# small_esc.net
KiCad netlist of a schematic drawn in EAGLE
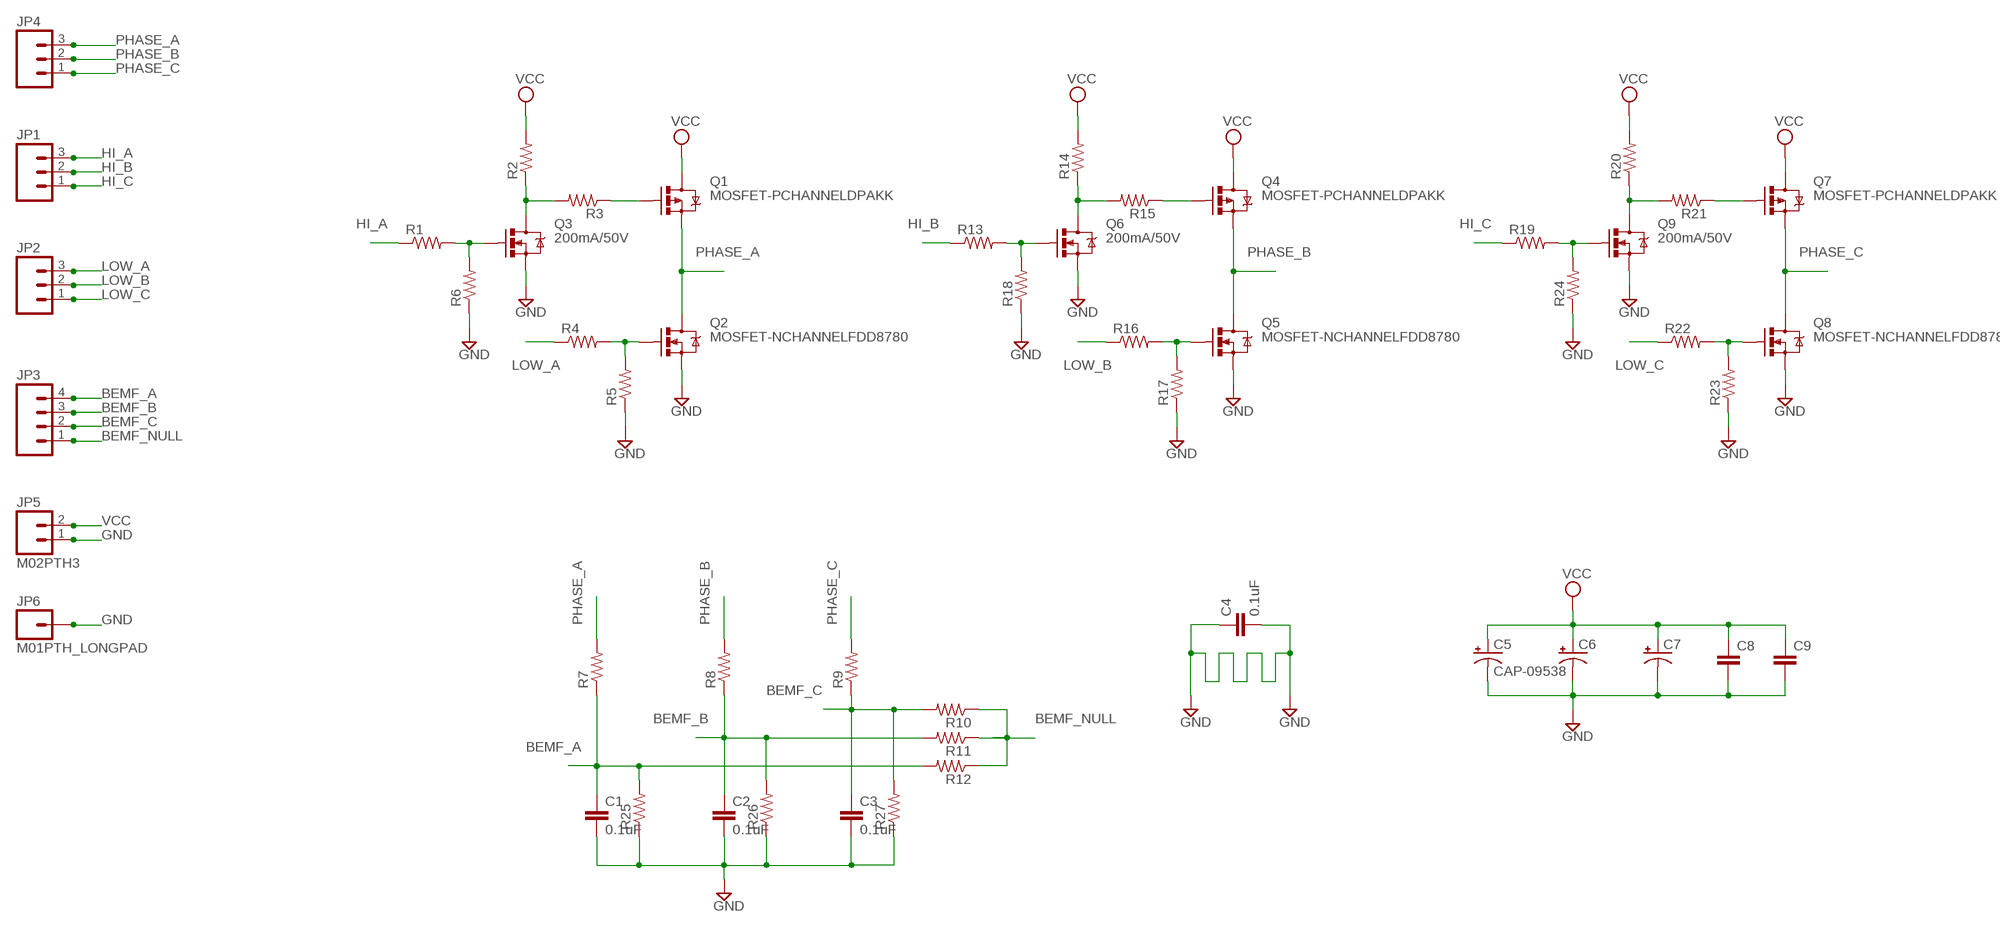
[diagram p0: schematic, sheet 1]

(export (version "E")
  (design (tool "Eeschema 10.0.6"))
  (components
    (comp (ref "C1")
      (value "0.1uF")
      (footprint "eagle-import:0603-CAP")
      (libsource (lib "eagle-import") (part "0.1UF-25V(+80/-20%)(0603)"))
    )
    (comp (ref "C2")
      (value "0.1uF")
      (footprint "eagle-import:0603-CAP")
      (libsource (lib "eagle-import") (part "0.1UF-25V(+80/-20%)(0603)"))
    )
    (comp (ref "C3")
      (value "0.1uF")
      (footprint "eagle-import:0603-CAP")
      (libsource (lib "eagle-import") (part "0.1UF-25V(+80/-20%)(0603)"))
    )
    (comp (ref "C4")
      (value "0.1uF")
      (footprint "eagle-import:0603-CAP")
      (libsource (lib "eagle-import") (part "0.1UF-25V(+80/-20%)(0603)"))
    )
    (comp (ref "C5")
      (value "CAP-09538")
      (footprint "eagle-import:CPOL-RADIAL-1000UF-25V")
      (libsource (lib "eagle-import") (part "1000UF-25V(PTH)"))
    )
    (comp (ref "C6")
      (value "CAP_POLPTH2")
      (footprint "eagle-import:CPOL-RADIAL-10UF-25V")
      (libsource (lib "eagle-import") (part "CAP_POLPTH2"))
    )
    (comp (ref "C7")
      (value "CAP_POLPTH2")
      (footprint "eagle-import:CPOL-RADIAL-10UF-25V")
      (libsource (lib "eagle-import") (part "CAP_POLPTH2"))
    )
    (comp (ref "C8")
      (value "0.1UF-50V-20%(PTH)KIT-EZ")
      (footprint "eagle-import:CAP-PTH-SMALL-KIT")
      (libsource (lib "eagle-import") (part "0.1UF-50V-20%(PTH)KIT-EZ"))
    )
    (comp (ref "C9")
      (value "0.1UF-50V-20%(PTH)KIT-EZ")
      (footprint "eagle-import:CAP-PTH-SMALL-KIT")
      (libsource (lib "eagle-import") (part "0.1UF-50V-20%(PTH)KIT-EZ"))
    )
    (comp (ref "JP1")
      (value "M03LONGPADS")
      (footprint "eagle-import:1X03_LONGPADS")
      (libsource (lib "eagle-import") (part "M03LONGPADS"))
    )
    (comp (ref "JP2")
      (value "M03LONGPADS")
      (footprint "eagle-import:1X03_LONGPADS")
      (libsource (lib "eagle-import") (part "M03LONGPADS"))
    )
    (comp (ref "JP3")
      (value "M04LONGPADS")
      (footprint "eagle-import:1X04_LONGPADS")
      (libsource (lib "eagle-import") (part "M04LONGPADS"))
    )
    (comp (ref "JP4")
      (value "M03LONGPADS")
      (footprint "eagle-import:1X03_LONGPADS")
      (libsource (lib "eagle-import") (part "M03LONGPADS"))
    )
    (comp (ref "JP5")
      (value "M02PTH3")
      (footprint "eagle-import:1X02_LONGPADS")
      (libsource (lib "eagle-import") (part "M02PTH3"))
    )
    (comp (ref "JP6")
      (value "M01PTH_LONGPAD")
      (footprint "eagle-import:1X01_LONGPAD")
      (libsource (lib "eagle-import") (part "M01PTH_LONGPAD"))
    )
    (comp (ref "Q1")
      (value "MOSFET-PCHANNELDPAKK")
      (footprint "eagle-import:DPAK")
      (libsource (lib "eagle-import") (part "MOSFET-PCHANNELDPAKK"))
    )
    (comp (ref "Q2")
      (value "MOSFET-NCHANNELFDD8780")
      (footprint "eagle-import:DPAK")
      (libsource (lib "eagle-import") (part "MOSFET-NCHANNELFDD8780"))
    )
    (comp (ref "Q3")
      (value "200mA/50V")
      (footprint "eagle-import:SOT23-3")
      (libsource (lib "eagle-import") (part "MOSFET-NCHANNELBSS138"))
    )
    (comp (ref "Q4")
      (value "MOSFET-PCHANNELDPAKK")
      (footprint "eagle-import:DPAK")
      (libsource (lib "eagle-import") (part "MOSFET-PCHANNELDPAKK"))
    )
    (comp (ref "Q5")
      (value "MOSFET-NCHANNELFDD8780")
      (footprint "eagle-import:DPAK")
      (libsource (lib "eagle-import") (part "MOSFET-NCHANNELFDD8780"))
    )
    (comp (ref "Q6")
      (value "200mA/50V")
      (footprint "eagle-import:SOT23-3")
      (libsource (lib "eagle-import") (part "MOSFET-NCHANNELBSS138"))
    )
    (comp (ref "Q7")
      (value "MOSFET-PCHANNELDPAKK")
      (footprint "eagle-import:DPAK")
      (libsource (lib "eagle-import") (part "MOSFET-PCHANNELDPAKK"))
    )
    (comp (ref "Q8")
      (value "MOSFET-NCHANNELFDD8780")
      (footprint "eagle-import:DPAK")
      (libsource (lib "eagle-import") (part "MOSFET-NCHANNELFDD8780"))
    )
    (comp (ref "Q9")
      (value "200mA/50V")
      (footprint "eagle-import:SOT23-3")
      (libsource (lib "eagle-import") (part "MOSFET-NCHANNELBSS138"))
    )
    (comp (ref "R1")
      (value "RESISTOR0603")
      (footprint "eagle-import:0603-RES")
      (libsource (lib "eagle-import") (part "RESISTOR0603"))
    )
    (comp (ref "R2")
      (value "RESISTOR0603")
      (footprint "eagle-import:0603-RES")
      (libsource (lib "eagle-import") (part "RESISTOR0603"))
    )
    (comp (ref "R3")
      (value "RESISTOR0603")
      (footprint "eagle-import:0603-RES")
      (libsource (lib "eagle-import") (part "RESISTOR0603"))
    )
    (comp (ref "R4")
      (value "RESISTOR0603")
      (footprint "eagle-import:0603-RES")
      (libsource (lib "eagle-import") (part "RESISTOR0603"))
    )
    (comp (ref "R5")
      (value "RESISTOR0603")
      (footprint "eagle-import:0603-RES")
      (libsource (lib "eagle-import") (part "RESISTOR0603"))
    )
    (comp (ref "R6")
      (value "RESISTOR0603")
      (footprint "eagle-import:0603-RES")
      (libsource (lib "eagle-import") (part "RESISTOR0603"))
    )
    (comp (ref "R7")
      (value "RESISTOR0603")
      (footprint "eagle-import:0603-RES")
      (libsource (lib "eagle-import") (part "RESISTOR0603"))
    )
    (comp (ref "R8")
      (value "RESISTOR0603")
      (footprint "eagle-import:0603-RES")
      (libsource (lib "eagle-import") (part "RESISTOR0603"))
    )
    (comp (ref "R9")
      (value "RESISTOR0603")
      (footprint "eagle-import:0603-RES")
      (libsource (lib "eagle-import") (part "RESISTOR0603"))
    )
    (comp (ref "R10")
      (value "RESISTOR0603")
      (footprint "eagle-import:0603-RES")
      (libsource (lib "eagle-import") (part "RESISTOR0603"))
    )
    (comp (ref "R11")
      (value "RESISTOR0603")
      (footprint "eagle-import:0603-RES")
      (libsource (lib "eagle-import") (part "RESISTOR0603"))
    )
    (comp (ref "R12")
      (value "RESISTOR0603")
      (footprint "eagle-import:0603-RES")
      (libsource (lib "eagle-import") (part "RESISTOR0603"))
    )
    (comp (ref "R13")
      (value "RESISTOR0603")
      (footprint "eagle-import:0603-RES")
      (libsource (lib "eagle-import") (part "RESISTOR0603"))
    )
    (comp (ref "R14")
      (value "RESISTOR0603")
      (footprint "eagle-import:0603-RES")
      (libsource (lib "eagle-import") (part "RESISTOR0603"))
    )
    (comp (ref "R15")
      (value "RESISTOR0603")
      (footprint "eagle-import:0603-RES")
      (libsource (lib "eagle-import") (part "RESISTOR0603"))
    )
    (comp (ref "R16")
      (value "RESISTOR0603")
      (footprint "eagle-import:0603-RES")
      (libsource (lib "eagle-import") (part "RESISTOR0603"))
    )
    (comp (ref "R17")
      (value "RESISTOR0603")
      (footprint "eagle-import:0603-RES")
      (libsource (lib "eagle-import") (part "RESISTOR0603"))
    )
    (comp (ref "R18")
      (value "RESISTOR0603")
      (footprint "eagle-import:0603-RES")
      (libsource (lib "eagle-import") (part "RESISTOR0603"))
    )
    (comp (ref "R19")
      (value "RESISTOR0603")
      (footprint "eagle-import:0603-RES")
      (libsource (lib "eagle-import") (part "RESISTOR0603"))
    )
    (comp (ref "R20")
      (value "RESISTOR0603")
      (footprint "eagle-import:0603-RES")
      (libsource (lib "eagle-import") (part "RESISTOR0603"))
    )
    (comp (ref "R21")
      (value "RESISTOR0603")
      (footprint "eagle-import:0603-RES")
      (libsource (lib "eagle-import") (part "RESISTOR0603"))
    )
    (comp (ref "R22")
      (value "RESISTOR0603")
      (footprint "eagle-import:0603-RES")
      (libsource (lib "eagle-import") (part "RESISTOR0603"))
    )
    (comp (ref "R23")
      (value "RESISTOR0603")
      (footprint "eagle-import:0603-RES")
      (libsource (lib "eagle-import") (part "RESISTOR0603"))
    )
    (comp (ref "R24")
      (value "RESISTOR0603")
      (footprint "eagle-import:0603-RES")
      (libsource (lib "eagle-import") (part "RESISTOR0603"))
    )
    (comp (ref "R25")
      (value "RESISTOR0603")
      (footprint "eagle-import:0603-RES")
      (libsource (lib "eagle-import") (part "RESISTOR0603"))
    )
    (comp (ref "R26")
      (value "RESISTOR0603")
      (footprint "eagle-import:0603-RES")
      (libsource (lib "eagle-import") (part "RESISTOR0603"))
    )
    (comp (ref "R27")
      (value "RESISTOR0603")
      (footprint "eagle-import:0603-RES")
      (libsource (lib "eagle-import") (part "RESISTOR0603"))
    )
  )
  (nets
    (net (code "1") (name "/BEMF_A") (class "Default")
      (node (ref "C1") (pin "1") (pinfunction "1_1") (pintype "passive"))
      (node (ref "JP3") (pin "4") (pinfunction "4_4") (pintype "passive"))
      (node (ref "R12") (pin "2") (pinfunction "2_2") (pintype "passive"))
      (node (ref "R25") (pin "2") (pinfunction "2_2") (pintype "passive"))
      (node (ref "R7") (pin "1") (pinfunction "1_1") (pintype "passive"))
    )
    (net (code "2") (name "/BEMF_B") (class "Default")
      (node (ref "C2") (pin "1") (pinfunction "1_1") (pintype "passive"))
      (node (ref "JP3") (pin "3") (pinfunction "3_3") (pintype "passive"))
      (node (ref "R11") (pin "2") (pinfunction "2_2") (pintype "passive"))
      (node (ref "R26") (pin "2") (pinfunction "2_2") (pintype "passive"))
      (node (ref "R8") (pin "1") (pinfunction "1_1") (pintype "passive"))
    )
    (net (code "3") (name "/BEMF_C") (class "Default")
      (node (ref "C3") (pin "1") (pinfunction "1_1") (pintype "passive"))
      (node (ref "JP3") (pin "2") (pinfunction "2_2") (pintype "passive"))
      (node (ref "R10") (pin "2") (pinfunction "2_2") (pintype "passive"))
      (node (ref "R27") (pin "2") (pinfunction "2_2") (pintype "passive"))
      (node (ref "R9") (pin "1") (pinfunction "1_1") (pintype "passive"))
    )
    (net (code "4") (name "/BEMF_NULL") (class "Default")
      (node (ref "JP3") (pin "1") (pinfunction "1_1") (pintype "passive"))
      (node (ref "R10") (pin "1") (pinfunction "1_1") (pintype "passive"))
      (node (ref "R11") (pin "1") (pinfunction "1_1") (pintype "passive"))
      (node (ref "R12") (pin "1") (pinfunction "1_1") (pintype "passive"))
    )
    (net (code "5") (name "/HI_A") (class "Default")
      (node (ref "JP1") (pin "3") (pinfunction "3_3") (pintype "passive"))
      (node (ref "R1") (pin "1") (pinfunction "1_1") (pintype "passive"))
    )
    (net (code "6") (name "/HI_B") (class "Default")
      (node (ref "JP1") (pin "2") (pinfunction "2_2") (pintype "passive"))
      (node (ref "R13") (pin "1") (pinfunction "1_1") (pintype "passive"))
    )
    (net (code "7") (name "/HI_C") (class "Default")
      (node (ref "JP1") (pin "1") (pinfunction "1_1") (pintype "passive"))
      (node (ref "R19") (pin "1") (pinfunction "1_1") (pintype "passive"))
    )
    (net (code "8") (name "/LOW_A") (class "Default")
      (node (ref "JP2") (pin "3") (pinfunction "3_3") (pintype "passive"))
      (node (ref "R4") (pin "1") (pinfunction "1_1") (pintype "passive"))
    )
    (net (code "9") (name "/LOW_B") (class "Default")
      (node (ref "JP2") (pin "2") (pinfunction "2_2") (pintype "passive"))
      (node (ref "R16") (pin "1") (pinfunction "1_1") (pintype "passive"))
    )
    (net (code "10") (name "/LOW_C") (class "Default")
      (node (ref "JP2") (pin "1") (pinfunction "1_1") (pintype "passive"))
      (node (ref "R22") (pin "1") (pinfunction "1_1") (pintype "passive"))
    )
    (net (code "11") (name "/PHASE_A") (class "Default")
      (node (ref "JP4") (pin "3") (pinfunction "3_3") (pintype "passive"))
      (node (ref "Q1") (pin "4") (pinfunction "S_4") (pintype "passive"))
      (node (ref "Q2") (pin "4") (pinfunction "D_4") (pintype "passive"))
      (node (ref "R7") (pin "2") (pinfunction "2_2") (pintype "passive"))
    )
    (net (code "12") (name "/PHASE_B") (class "Default")
      (node (ref "JP4") (pin "2") (pinfunction "2_2") (pintype "passive"))
      (node (ref "Q4") (pin "4") (pinfunction "S_4") (pintype "passive"))
      (node (ref "Q5") (pin "4") (pinfunction "D_4") (pintype "passive"))
      (node (ref "R8") (pin "2") (pinfunction "2_2") (pintype "passive"))
    )
    (net (code "13") (name "/PHASE_C") (class "Default")
      (node (ref "JP4") (pin "1") (pinfunction "1_1") (pintype "passive"))
      (node (ref "Q7") (pin "4") (pinfunction "S_4") (pintype "passive"))
      (node (ref "Q8") (pin "4") (pinfunction "D_4") (pintype "passive"))
      (node (ref "R9") (pin "2") (pinfunction "2_2") (pintype "passive"))
    )
    (net (code "14") (name "GND") (class "Default")
      (node (ref "C1") (pin "2") (pinfunction "2_2") (pintype "passive"))
      (node (ref "C2") (pin "2") (pinfunction "2_2") (pintype "passive"))
      (node (ref "C3") (pin "2") (pinfunction "2_2") (pintype "passive"))
      (node (ref "C4") (pin "1") (pinfunction "1_1") (pintype "passive"))
      (node (ref "C4") (pin "2") (pinfunction "2_2") (pintype "passive"))
      (node (ref "C5") (pin "-") (pinfunction "-_-") (pintype "passive"))
      (node (ref "C6") (pin "2") (pinfunction "-_2") (pintype "passive"))
      (node (ref "C7") (pin "2") (pinfunction "-_2") (pintype "passive"))
      (node (ref "C8") (pin "2") (pinfunction "2_2") (pintype "passive"))
      (node (ref "C9") (pin "2") (pinfunction "2_2") (pintype "passive"))
      (node (ref "JP5") (pin "1") (pinfunction "1_1") (pintype "passive"))
      (node (ref "JP6") (pin "1") (pinfunction "1_1") (pintype "passive"))
      (node (ref "Q2") (pin "3") (pinfunction "S_3") (pintype "passive"))
      (node (ref "Q3") (pin "2") (pinfunction "S_2") (pintype "passive"))
      (node (ref "Q5") (pin "3") (pinfunction "S_3") (pintype "passive"))
      (node (ref "Q6") (pin "2") (pinfunction "S_2") (pintype "passive"))
      (node (ref "Q8") (pin "3") (pinfunction "S_3") (pintype "passive"))
      (node (ref "Q9") (pin "2") (pinfunction "S_2") (pintype "passive"))
      (node (ref "R17") (pin "1") (pinfunction "1_1") (pintype "passive"))
      (node (ref "R18") (pin "1") (pinfunction "1_1") (pintype "passive"))
      (node (ref "R23") (pin "1") (pinfunction "1_1") (pintype "passive"))
      (node (ref "R24") (pin "1") (pinfunction "1_1") (pintype "passive"))
      (node (ref "R25") (pin "1") (pinfunction "1_1") (pintype "passive"))
      (node (ref "R26") (pin "1") (pinfunction "1_1") (pintype "passive"))
      (node (ref "R27") (pin "1") (pinfunction "1_1") (pintype "passive"))
      (node (ref "R5") (pin "1") (pinfunction "1_1") (pintype "passive"))
      (node (ref "R6") (pin "1") (pinfunction "1_1") (pintype "passive"))
    )
    (net (code "15") (name "Net-(Q1-G)") (class "Default")
      (node (ref "Q1") (pin "1") (pinfunction "G_1") (pintype "passive"))
      (node (ref "R3") (pin "1") (pinfunction "1_1") (pintype "passive"))
    )
    (net (code "16") (name "Net-(Q2-G)") (class "Default")
      (node (ref "Q2") (pin "1") (pinfunction "G_1") (pintype "passive"))
      (node (ref "R4") (pin "2") (pinfunction "2_2") (pintype "passive"))
      (node (ref "R5") (pin "2") (pinfunction "2_2") (pintype "passive"))
    )
    (net (code "17") (name "Net-(Q3-D)") (class "Default")
      (node (ref "Q3") (pin "3") (pinfunction "D_3") (pintype "passive"))
      (node (ref "R2") (pin "1") (pinfunction "1_1") (pintype "passive"))
      (node (ref "R3") (pin "2") (pinfunction "2_2") (pintype "passive"))
    )
    (net (code "18") (name "Net-(Q3-G)") (class "Default")
      (node (ref "Q3") (pin "1") (pinfunction "G_1") (pintype "passive"))
      (node (ref "R1") (pin "2") (pinfunction "2_2") (pintype "passive"))
      (node (ref "R6") (pin "2") (pinfunction "2_2") (pintype "passive"))
    )
    (net (code "19") (name "Net-(Q4-G)") (class "Default")
      (node (ref "Q4") (pin "1") (pinfunction "G_1") (pintype "passive"))
      (node (ref "R15") (pin "1") (pinfunction "1_1") (pintype "passive"))
    )
    (net (code "20") (name "Net-(Q5-G)") (class "Default")
      (node (ref "Q5") (pin "1") (pinfunction "G_1") (pintype "passive"))
      (node (ref "R16") (pin "2") (pinfunction "2_2") (pintype "passive"))
      (node (ref "R17") (pin "2") (pinfunction "2_2") (pintype "passive"))
    )
    (net (code "21") (name "Net-(Q6-D)") (class "Default")
      (node (ref "Q6") (pin "3") (pinfunction "D_3") (pintype "passive"))
      (node (ref "R14") (pin "1") (pinfunction "1_1") (pintype "passive"))
      (node (ref "R15") (pin "2") (pinfunction "2_2") (pintype "passive"))
    )
    (net (code "22") (name "Net-(Q6-G)") (class "Default")
      (node (ref "Q6") (pin "1") (pinfunction "G_1") (pintype "passive"))
      (node (ref "R13") (pin "2") (pinfunction "2_2") (pintype "passive"))
      (node (ref "R18") (pin "2") (pinfunction "2_2") (pintype "passive"))
    )
    (net (code "23") (name "Net-(Q7-G)") (class "Default")
      (node (ref "Q7") (pin "1") (pinfunction "G_1") (pintype "passive"))
      (node (ref "R21") (pin "1") (pinfunction "1_1") (pintype "passive"))
    )
    (net (code "24") (name "Net-(Q8-G)") (class "Default")
      (node (ref "Q8") (pin "1") (pinfunction "G_1") (pintype "passive"))
      (node (ref "R22") (pin "2") (pinfunction "2_2") (pintype "passive"))
      (node (ref "R23") (pin "2") (pinfunction "2_2") (pintype "passive"))
    )
    (net (code "25") (name "Net-(Q9-D)") (class "Default")
      (node (ref "Q9") (pin "3") (pinfunction "D_3") (pintype "passive"))
      (node (ref "R20") (pin "1") (pinfunction "1_1") (pintype "passive"))
      (node (ref "R21") (pin "2") (pinfunction "2_2") (pintype "passive"))
    )
    (net (code "26") (name "Net-(Q9-G)") (class "Default")
      (node (ref "Q9") (pin "1") (pinfunction "G_1") (pintype "passive"))
      (node (ref "R19") (pin "2") (pinfunction "2_2") (pintype "passive"))
      (node (ref "R24") (pin "2") (pinfunction "2_2") (pintype "passive"))
    )
    (net (code "27") (name "VCC") (class "Default")
      (node (ref "C5") (pin "+") (pinfunction "+_+") (pintype "passive"))
      (node (ref "C6") (pin "1") (pinfunction "+_1") (pintype "passive"))
      (node (ref "C7") (pin "1") (pinfunction "+_1") (pintype "passive"))
      (node (ref "C8") (pin "1") (pinfunction "1_1") (pintype "passive"))
      (node (ref "C9") (pin "1") (pinfunction "1_1") (pintype "passive"))
      (node (ref "JP5") (pin "2") (pinfunction "2_2") (pintype "passive"))
      (node (ref "Q1") (pin "3") (pinfunction "D_3") (pintype "passive"))
      (node (ref "Q4") (pin "3") (pinfunction "D_3") (pintype "passive"))
      (node (ref "Q7") (pin "3") (pinfunction "D_3") (pintype "passive"))
      (node (ref "R14") (pin "2") (pinfunction "2_2") (pintype "passive"))
      (node (ref "R2") (pin "2") (pinfunction "2_2") (pintype "passive"))
      (node (ref "R20") (pin "2") (pinfunction "2_2") (pintype "passive"))
    )
  )
)
